# lazer-sensor-for-trespassers.net
KiCad netlist of a schematic drawn in Altium Designer
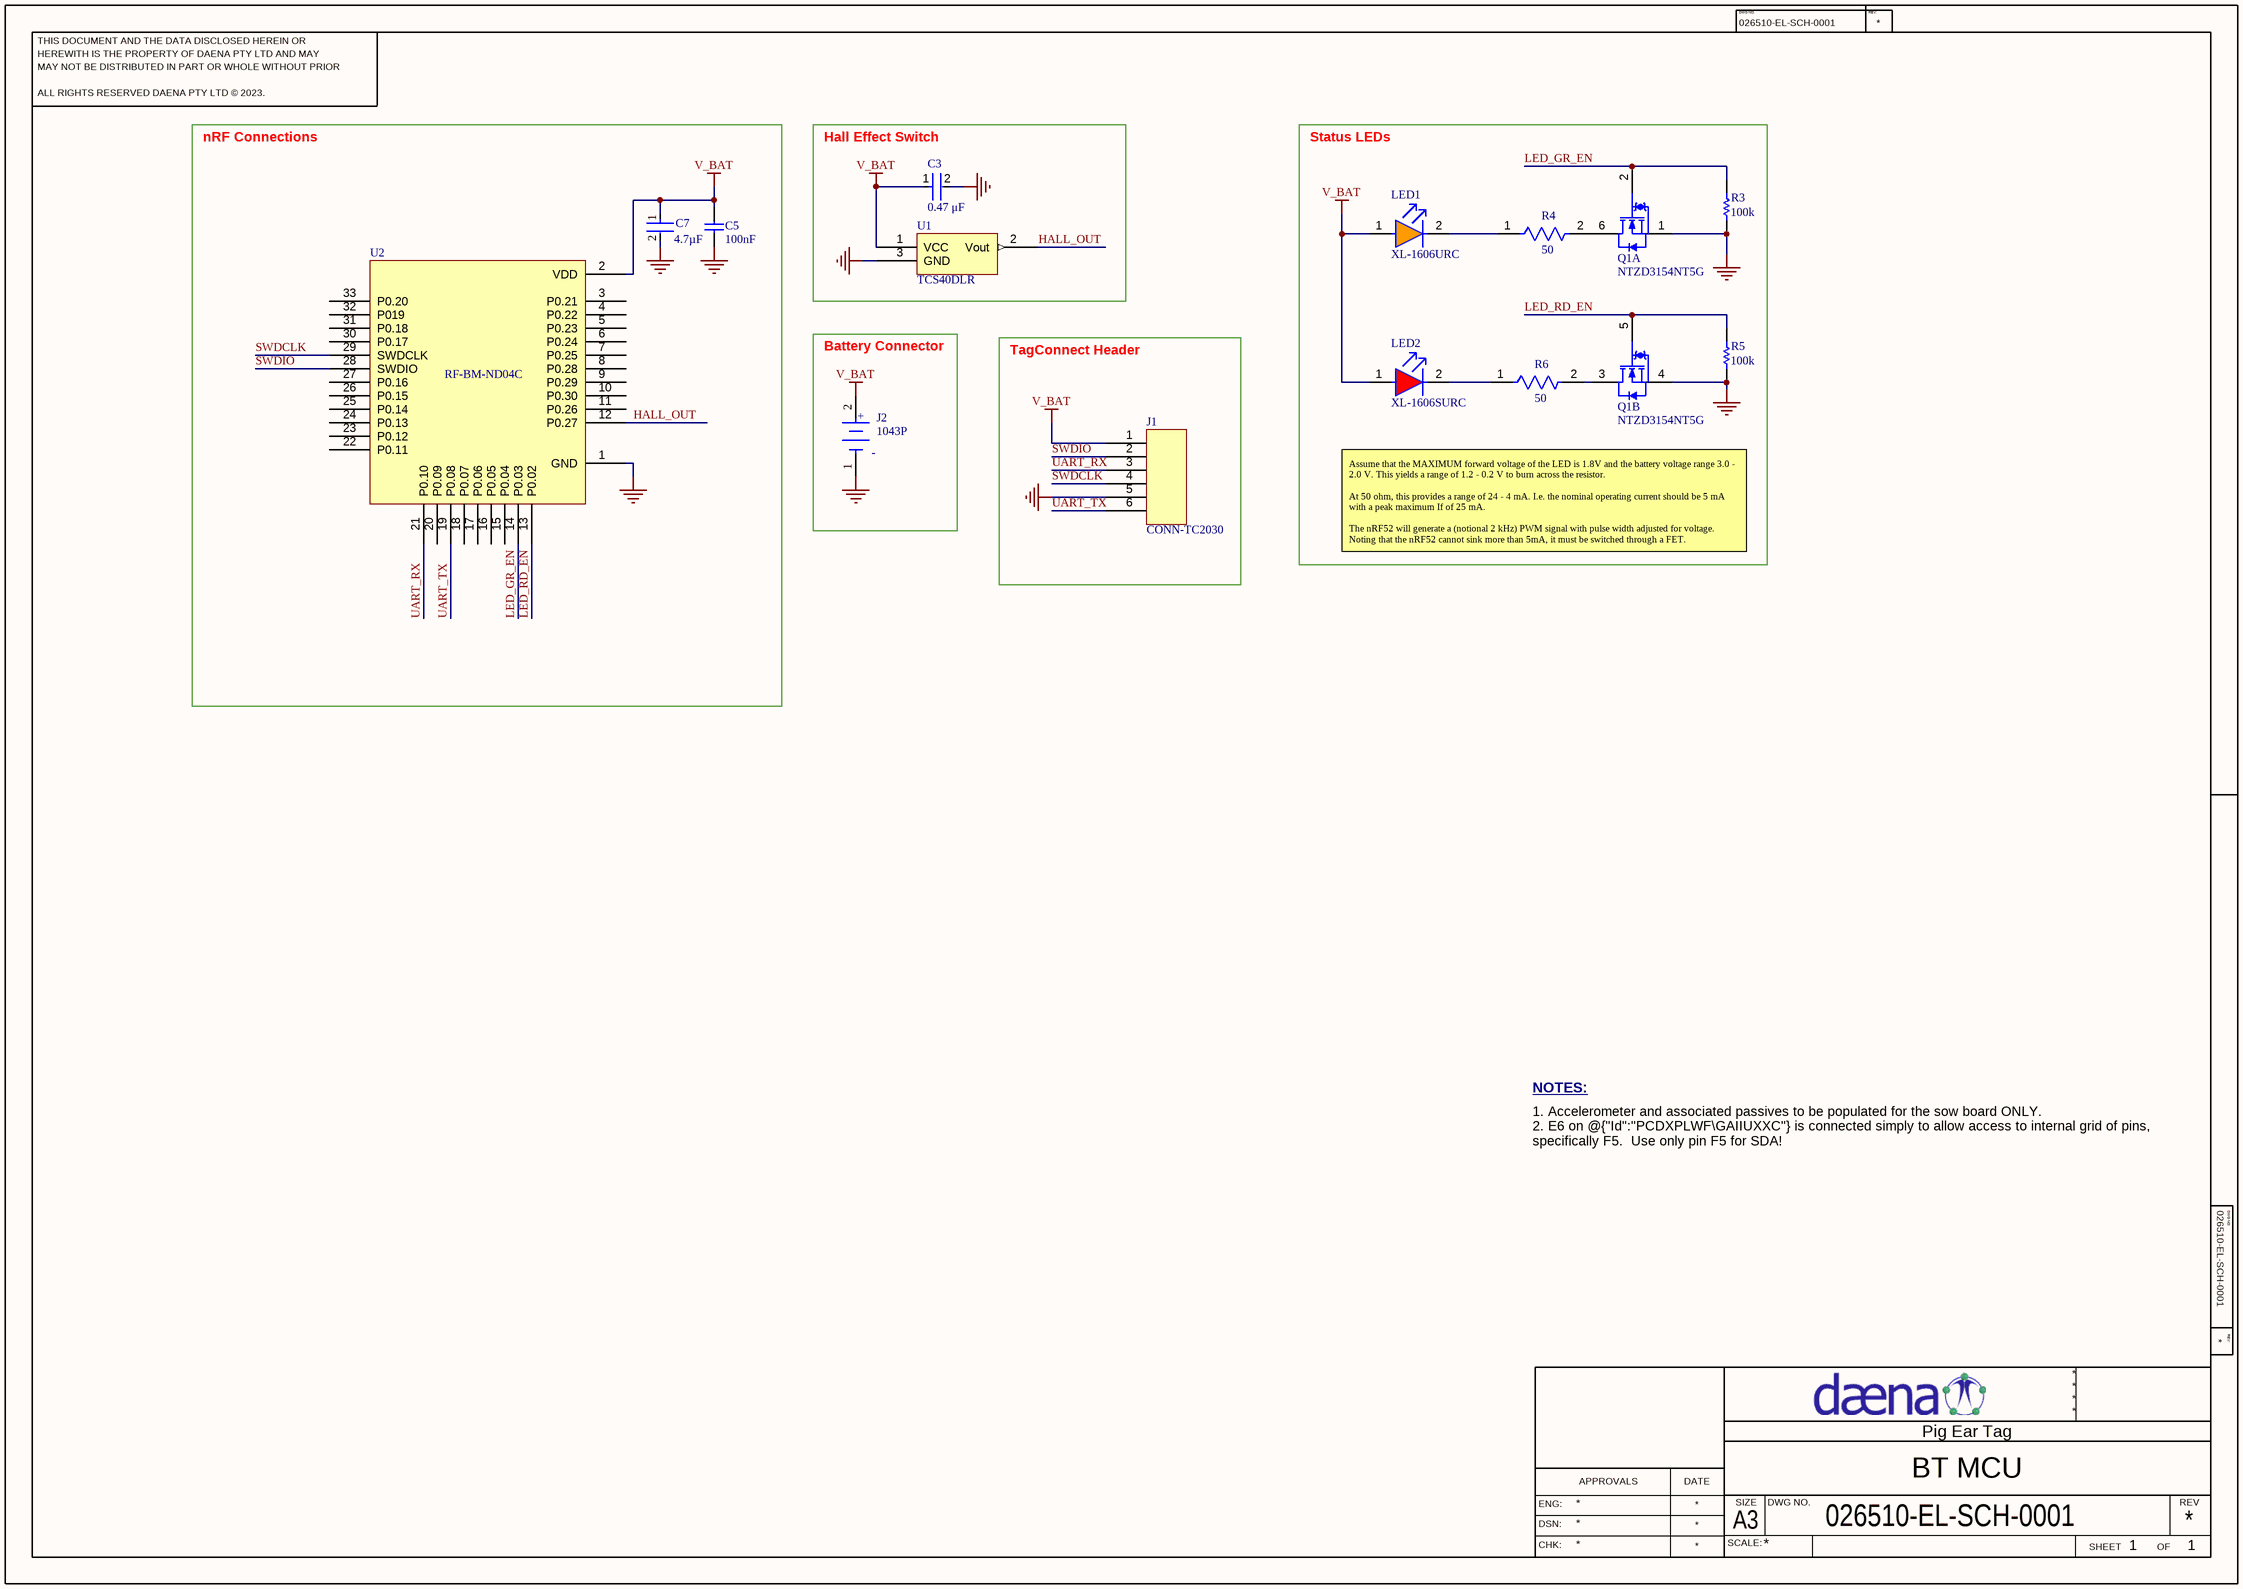
[diagram p0: lazer-sensor-for-trespassers.SchDoc]

(export (version "E")
  (design (tool "Eeschema 10.0.6"))
  (components
    (comp (ref "C3")
      (value "0.47 μF")
      (footprint "FP-C0805C-DN-MFG")
      (description "CAP CER 0.47UF 25V X7R 0805")
      (fields (field (name "TOLERANCE") "0.1") (field (name "MANUFACTURER") "KEMET"))
      (libsource (lib "Altium Content Vault") (part "b4654b650e69147ec39a6b967a45e02"))
    )
    (comp (ref "C5")
      (value "100nF")
      (footprint "CAPC0603X03L_C")
      (description "Capacitor, X5R, ±10%")
      (fields (field (name "PART NUMBER") "C0201-100n") (field (name "PUBLISHER") "Nordic Semiconductor"))
      (libsource (lib "lazer-sensor-for-trespassers") (part "CAP"))
    )
    (comp (ref "C7")
      (value "GRM188R61C475KAAJD")
      (footprint "FP-GRM188-0_15-MFG")
      (description "CAP CER 4.7UF 16V X5R 0603")
      (fields (field (name "CAPACITANCE") "4.7µF") (field (name "TOLERANCE") "10%"))
      (libsource (lib "Altium Content Vault") (part "02cd4be3c70576c341d710602a673aa"))
    )
    (comp (ref "J1")
      (value "CONN-TC2030")
      (footprint "TC2030-IDC-PLUG-OF-NAILS-TIGHT")
      (description "TC2030 PLUG-OF-NAILS CABLE")
      (libsource (lib "lazer-sensor-for-trespassers") (part "CONN-TC2030"))
    )
    (comp (ref "J2")
      (value "1043P")
      (footprint "FP-1043P-MFG")
      (description "BATT HOLDER 18650 1 CELL PC PIN")
      (libsource (lib "Altium Content Vault") (part "60d3b5b901a8747834971d0eb8cf3fd"))
    )
    (comp (ref "LED1")
      (value "XL-1606URC")
      (footprint "LED-RA-1606")
      (description "Orange LED 90° mount")
      (libsource (lib "lazer-sensor-for-trespassers") (part "LED-ORANGE-RA"))
    )
    (comp (ref "LED2")
      (value "XL-1606SURC")
      (footprint "LED-RA-1606")
      (description "Red LED 90° mount")
      (libsource (lib "lazer-sensor-for-trespassers") (part "LED-RED-RA"))
    )
    (comp (ref "Q1")
      (value "NTZD3154NT5G")
      (footprint "ONSC-SOT-563-6-463A-01_V")
      (description "Small Signal MOSFET, 20 V, 540 mA, Dual N-Channel, 6-Pin SOT-563, Pb-Free, Tape and Reel")
      (fields (field (name "MANUFACTURER") "On Semiconductor"))
      (libsource (lib "Altium Content Vault") (part "ONSC-NNMOS-6_F"))
    )
    (comp (ref "R3")
      (value "100k")
      (footprint "RESC1005X40X25ML05T10")
      (fields (field (name "PART NUMBER") "RC0402FR-07100KL") (field (name "MANUFACTURER") "Yageo / Phycomp"))
      (libsource (lib "Altium Content Vault") (part "RES"))
    )
    (comp (ref "R4")
      (value "AC0402JR-0750RL")
      (footprint "FP-AC0402-IPC_C")
      (description "RES 50Ω ±5% 0.063W 0402")
      (fields (field (name "TOLERANCE") "5%") (field (name "RESISTANCE") "50"))
      (libsource (lib "Altium Content Vault") (part "1029c3af85768c4190bb7ad29bc67b5"))
    )
    (comp (ref "R5")
      (value "100k")
      (footprint "RESC1005X40X25ML05T10")
      (fields (field (name "PART NUMBER") "RC0402FR-07100KL") (field (name "MANUFACTURER") "Yageo / Phycomp"))
      (libsource (lib "Altium Content Vault") (part "RES"))
    )
    (comp (ref "R6")
      (value "AC0402JR-0750RL")
      (footprint "FP-AC0402-IPC_C")
      (description "RES 50Ω ±5% 0.063W 0402")
      (fields (field (name "TOLERANCE") "5%") (field (name "RESISTANCE") "50"))
      (libsource (lib "Altium Content Vault") (part "1029c3af85768c4190bb7ad29bc67b5"))
    )
    (comp (ref "U1")
      (value "TCS40DLR")
      (footprint "SOT95P245X80-3N")
      (description "Digital-Output Magnetic Sensor (Hall IC). Open drain.")
      (libsource (lib "lazer-sensor-for-trespassers") (part "IC-HALL-TCS40DLR"))
    )
    (comp (ref "U2")
      (value "RF-BM-ND04C")
      (footprint "RF-BM-ND04")
      (description "nRF52810-based Bluetooth 5.0 Low Energy module with internal 32 MHz and 32.768 kHz crystals.")
      (libsource (lib "lazer-sensor-for-trespassers") (part "RF-BM-ND04C"))
    )
  )
  (nets
    (net (code "1") (name "/HALL_OUT") (class "Default")
      (node (ref "U1") (pin "2") (pinfunction "Vout_2") (pintype "output"))
      (node (ref "U2") (pin "12") (pinfunction "P0.27_12") (pintype "passive"))
    )
    (net (code "2") (name "/LED_GR_EN") (class "Default")
      (node (ref "Q1") (pin "2") (pinfunction "G1_2") (pintype "passive"))
      (node (ref "R3") (pin "2") (pinfunction "2_2") (pintype "passive"))
      (node (ref "U2") (pin "14") (pinfunction "P0.03_14") (pintype "passive"))
    )
    (net (code "3") (name "/LED_RD_EN") (class "Default")
      (node (ref "Q1") (pin "5") (pinfunction "G2_5") (pintype "passive"))
      (node (ref "R5") (pin "2") (pinfunction "2_2") (pintype "passive"))
      (node (ref "U2") (pin "13") (pinfunction "P0.02_13") (pintype "passive"))
    )
    (net (code "4") (name "/SWDCLK") (class "Default")
      (node (ref "J1") (pin "4") (pintype "passive"))
      (node (ref "U2") (pin "29") (pinfunction "SWDCLK_29") (pintype "passive"))
    )
    (net (code "5") (name "/SWDIO") (class "Default")
      (node (ref "J1") (pin "2") (pintype "passive"))
      (node (ref "U2") (pin "28") (pinfunction "SWDIO_28") (pintype "passive"))
    )
    (net (code "6") (name "/UART_RX") (class "Default")
      (node (ref "J1") (pin "3") (pintype "passive"))
      (node (ref "U2") (pin "21") (pinfunction "P0.10_21") (pintype "passive"))
    )
    (net (code "7") (name "/UART_TX") (class "Default")
      (node (ref "J1") (pin "6") (pintype "passive"))
      (node (ref "U2") (pin "19") (pinfunction "P0.08_19") (pintype "passive"))
    )
    (net (code "8") (name "GND") (class "Default")
      (node (ref "C3") (pin "2") (pinfunction "2_2") (pintype "passive"))
      (node (ref "C5") (pin "2") (pinfunction "2_2") (pintype "passive"))
      (node (ref "C7") (pin "2") (pinfunction "2_2") (pintype "passive"))
      (node (ref "J1") (pin "5") (pintype "passive"))
      (node (ref "J2") (pin "1") (pinfunction "C_1") (pintype "passive"))
      (node (ref "Q1") (pin "1") (pinfunction "S1_1") (pintype "passive"))
      (node (ref "Q1") (pin "4") (pinfunction "S2_4") (pintype "passive"))
      (node (ref "R3") (pin "1") (pinfunction "1_1") (pintype "passive"))
      (node (ref "R5") (pin "1") (pinfunction "1_1") (pintype "passive"))
      (node (ref "U1") (pin "3") (pinfunction "GND_3") (pintype "power_in"))
      (node (ref "U2") (pin "1") (pinfunction "GND_1") (pintype "passive"))
    )
    (net (code "9") (name "Net-(LED1-C)") (class "Default")
      (node (ref "LED1") (pin "2") (pinfunction "C_2") (pintype "passive"))
      (node (ref "R4") (pin "1") (pinfunction "1_1") (pintype "passive"))
    )
    (net (code "10") (name "Net-(LED2-C)") (class "Default")
      (node (ref "LED2") (pin "2") (pinfunction "C_2") (pintype "passive"))
      (node (ref "R6") (pin "1") (pinfunction "1_1") (pintype "passive"))
    )
    (net (code "11") (name "Net-(Q1A-D1)") (class "Default")
      (node (ref "Q1") (pin "6") (pinfunction "D1_6") (pintype "passive"))
      (node (ref "R4") (pin "2") (pinfunction "2_2") (pintype "passive"))
    )
    (net (code "12") (name "Net-(Q1B-D2)") (class "Default")
      (node (ref "Q1") (pin "3") (pinfunction "D2_3") (pintype "passive"))
      (node (ref "R6") (pin "2") (pinfunction "2_2") (pintype "passive"))
    )
    (net (code "13") (name "V_BAT") (class "Default")
      (node (ref "C3") (pin "1") (pinfunction "1_1") (pintype "passive"))
      (node (ref "C5") (pin "1") (pinfunction "1_1") (pintype "passive"))
      (node (ref "C7") (pin "1") (pinfunction "1_1") (pintype "passive"))
      (node (ref "J1") (pin "1") (pintype "passive"))
      (node (ref "J2") (pin "2") (pinfunction "A_2") (pintype "passive"))
      (node (ref "LED1") (pin "1") (pinfunction "A_1") (pintype "passive"))
      (node (ref "LED2") (pin "1") (pinfunction "A_1") (pintype "passive"))
      (node (ref "U1") (pin "1") (pinfunction "VCC_1") (pintype "power_in"))
      (node (ref "U2") (pin "2") (pinfunction "VDD_2") (pintype "passive"))
    )
    (net (code "14") (name "unconnected-(U2-P0.04-Pad15)") (class "Default")
      (node (ref "U2") (pin "15") (pinfunction "P0.04_15") (pintype "passive"))
    )
    (net (code "15") (name "unconnected-(U2-P0.05-Pad16)") (class "Default")
      (node (ref "U2") (pin "16") (pinfunction "P0.05_16") (pintype "passive"))
    )
    (net (code "16") (name "unconnected-(U2-P0.06-Pad17)") (class "Default")
      (node (ref "U2") (pin "17") (pinfunction "P0.06_17") (pintype "passive"))
    )
    (net (code "17") (name "unconnected-(U2-P0.07-Pad18)") (class "Default")
      (node (ref "U2") (pin "18") (pinfunction "P0.07_18") (pintype "passive"))
    )
    (net (code "18") (name "unconnected-(U2-P0.09-Pad20)") (class "Default")
      (node (ref "U2") (pin "20") (pinfunction "P0.09_20") (pintype "passive"))
    )
    (net (code "19") (name "unconnected-(U2-P0.11-Pad22)") (class "Default")
      (node (ref "U2") (pin "22") (pinfunction "P0.11_22") (pintype "passive"))
    )
    (net (code "20") (name "unconnected-(U2-P0.12-Pad23)") (class "Default")
      (node (ref "U2") (pin "23") (pinfunction "P0.12_23") (pintype "passive"))
    )
    (net (code "21") (name "unconnected-(U2-P0.13-Pad24)") (class "Default")
      (node (ref "U2") (pin "24") (pinfunction "P0.13_24") (pintype "passive"))
    )
    (net (code "22") (name "unconnected-(U2-P0.14-Pad25)") (class "Default")
      (node (ref "U2") (pin "25") (pinfunction "P0.14_25") (pintype "passive"))
    )
    (net (code "23") (name "unconnected-(U2-P0.15-Pad26)") (class "Default")
      (node (ref "U2") (pin "26") (pinfunction "P0.15_26") (pintype "passive"))
    )
    (net (code "24") (name "unconnected-(U2-P0.16-Pad27)") (class "Default")
      (node (ref "U2") (pin "27") (pinfunction "P0.16_27") (pintype "passive"))
    )
    (net (code "25") (name "unconnected-(U2-P0.17-Pad30)") (class "Default")
      (node (ref "U2") (pin "30") (pinfunction "P0.17_30") (pintype "passive"))
    )
    (net (code "26") (name "unconnected-(U2-P0.18-Pad31)") (class "Default")
      (node (ref "U2") (pin "31") (pinfunction "P0.18_31") (pintype "passive"))
    )
    (net (code "27") (name "unconnected-(U2-P0.20-Pad33)") (class "Default")
      (node (ref "U2") (pin "33") (pinfunction "P0.20_33") (pintype "passive"))
    )
    (net (code "28") (name "unconnected-(U2-P0.21-Pad3)") (class "Default")
      (node (ref "U2") (pin "3") (pinfunction "P0.21_3") (pintype "passive"))
    )
    (net (code "29") (name "unconnected-(U2-P0.22-Pad4)") (class "Default")
      (node (ref "U2") (pin "4") (pinfunction "P0.22_4") (pintype "passive"))
    )
    (net (code "30") (name "unconnected-(U2-P0.23-Pad5)") (class "Default")
      (node (ref "U2") (pin "5") (pinfunction "P0.23_5") (pintype "passive"))
    )
    (net (code "31") (name "unconnected-(U2-P0.24-Pad6)") (class "Default")
      (node (ref "U2") (pin "6") (pinfunction "P0.24_6") (pintype "passive"))
    )
    (net (code "32") (name "unconnected-(U2-P0.25-Pad7)") (class "Default")
      (node (ref "U2") (pin "7") (pinfunction "P0.25_7") (pintype "passive"))
    )
    (net (code "33") (name "unconnected-(U2-P0.26-Pad11)") (class "Default")
      (node (ref "U2") (pin "11") (pinfunction "P0.26_11") (pintype "passive"))
    )
    (net (code "34") (name "unconnected-(U2-P0.28-Pad8)") (class "Default")
      (node (ref "U2") (pin "8") (pinfunction "P0.28_8") (pintype "passive"))
    )
    (net (code "35") (name "unconnected-(U2-P0.29-Pad9)") (class "Default")
      (node (ref "U2") (pin "9") (pinfunction "P0.29_9") (pintype "passive"))
    )
    (net (code "36") (name "unconnected-(U2-P0.30-Pad10)") (class "Default")
      (node (ref "U2") (pin "10") (pinfunction "P0.30_10") (pintype "passive"))
    )
    (net (code "37") (name "unconnected-(U2-P019-Pad32)") (class "Default")
      (node (ref "U2") (pin "32") (pinfunction "P019_32") (pintype "passive"))
    )
  )
)
